# led_VDC.net
KiCad netlist of a schematic drawn in Altium Designer
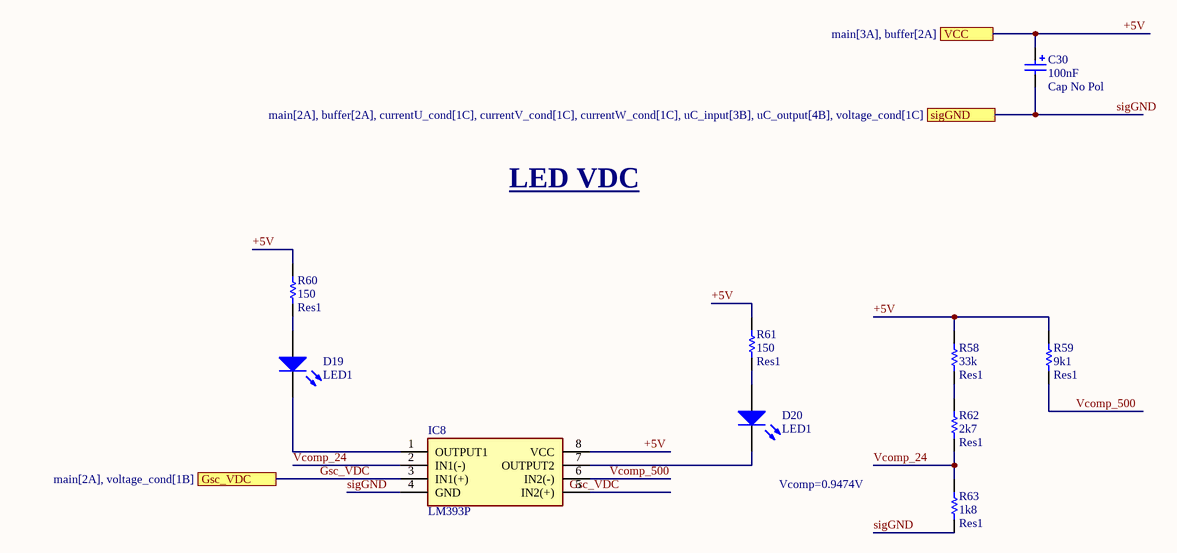
[diagram p0: led_VDC.SchDoc]

(export (version "E")
  (design (tool "Eeschema 10.0.6"))
  (components
    (comp (ref "C30")
      (value "Cap No Pol")
      (footprint "RAD-0.1_mod")
      (description "Polarized Capacitor (Radial)")
      (fields (field (name "ALTIUM_VALUE") "100nF") (field (name "PUBLISHER") "Altium Limited"))
      (libsource (lib "LABSTEPS_Project") (part "Cap No Pol"))
    )
    (comp (ref "D19")
      (value "LED1")
      (footprint "PIN2_mod")
      (description "Typical RED GaAs LED")
      (fields (field (name "PUBLISHER") "Altium Limited"))
      (libsource (lib "moded_symbol") (part "LED1"))
    )
    (comp (ref "D20")
      (value "LED1")
      (footprint "PIN2_mod")
      (description "Typical RED GaAs LED")
      (fields (field (name "PUBLISHER") "Altium Limited"))
      (libsource (lib "moded_symbol") (part "LED1"))
    )
    (comp (ref "IC8")
      (value "LM393P")
      (footprint "DIP-8_mod")
      (description "Integrated Circuit")
      (fields
        (field (name "MANUFACTURER_PART_NUMBER") "LM393N")
        (field (name "MOUSER PART NUMBER") "926-LM393N")
      )
      (libsource (lib "SamacSys") (part "LM393N"))
    )
    (comp (ref "R58")
      (value "Res1")
      (footprint "AXIAL-0.3_mod")
      (description "Resistor")
      (fields (field (name "ALTIUM_VALUE") "33k") (field (name "PUBLISHER") "Altium Limited"))
      (libsource (lib "LABSTEPS_Project") (part "Res1"))
    )
    (comp (ref "R59")
      (value "Res1")
      (footprint "AXIAL-0.3_mod")
      (description "Resistor")
      (fields (field (name "ALTIUM_VALUE") "9k1") (field (name "PUBLISHER") "Altium Limited"))
      (libsource (lib "LABSTEPS_Project") (part "Res1"))
    )
    (comp (ref "R60")
      (value "Res1")
      (footprint "AXIAL-0.3_mod")
      (description "Resistor")
      (fields (field (name "ALTIUM_VALUE") "150") (field (name "PUBLISHER") "Altium Limited"))
      (libsource (lib "LABSTEPS_Project") (part "Res1"))
    )
    (comp (ref "R61")
      (value "Res1")
      (footprint "AXIAL-0.3_mod")
      (description "Resistor")
      (fields (field (name "ALTIUM_VALUE") "150") (field (name "PUBLISHER") "Altium Limited"))
      (libsource (lib "LABSTEPS_Project") (part "Res1"))
    )
    (comp (ref "R62")
      (value "Res1")
      (footprint "AXIAL-0.3_mod")
      (description "Resistor")
      (fields (field (name "ALTIUM_VALUE") "2k7") (field (name "PUBLISHER") "Altium Limited"))
      (libsource (lib "LABSTEPS_Project") (part "Res1"))
    )
    (comp (ref "R63")
      (value "Res1")
      (footprint "AXIAL-0.3_mod")
      (description "Resistor")
      (fields (field (name "ALTIUM_VALUE") "1k8") (field (name "PUBLISHER") "Altium Limited"))
      (libsource (lib "LABSTEPS_Project") (part "Res1"))
    )
  )
  (nets
    (net (code "1") (name "/+5V") (class "Default")
      (node (ref "C30") (pin "1") (pinfunction "1_1") (pintype "passive"))
      (node (ref "IC8") (pin "8") (pinfunction "VCC_8") (pintype "passive"))
      (node (ref "R58") (pin "2") (pinfunction "2_2") (pintype "passive"))
      (node (ref "R59") (pin "2") (pinfunction "2_2") (pintype "passive"))
      (node (ref "R60") (pin "2") (pinfunction "2_2") (pintype "passive"))
      (node (ref "R61") (pin "2") (pinfunction "2_2") (pintype "passive"))
    )
    (net (code "2") (name "/Gsc_VDC") (class "Default")
      (node (ref "IC8") (pin "3") (pinfunction "IN1(+)_3") (pintype "passive"))
      (node (ref "IC8") (pin "5") (pinfunction "IN2(+)_5") (pintype "passive"))
    )
    (net (code "3") (name "/Vcomp_24") (class "Default")
      (node (ref "IC8") (pin "2") (pinfunction "IN1(-)_2") (pintype "passive"))
      (node (ref "R62") (pin "1") (pinfunction "1_1") (pintype "passive"))
      (node (ref "R63") (pin "2") (pinfunction "2_2") (pintype "passive"))
    )
    (net (code "4") (name "/Vcomp_500") (class "Default")
      (node (ref "IC8") (pin "6") (pinfunction "IN2(-)_6") (pintype "passive"))
      (node (ref "R59") (pin "1") (pinfunction "1_1") (pintype "passive"))
    )
    (net (code "5") (name "/sigGND") (class "Default")
      (node (ref "C30") (pin "2") (pinfunction "2_2") (pintype "passive"))
      (node (ref "IC8") (pin "4") (pinfunction "GND_4") (pintype "passive"))
      (node (ref "R63") (pin "1") (pinfunction "1_1") (pintype "passive"))
    )
    (net (code "6") (name "Net-(D19-A)") (class "Default")
      (node (ref "D19") (pin "1") (pinfunction "A_1") (pintype "passive"))
      (node (ref "R60") (pin "1") (pinfunction "1_1") (pintype "passive"))
    )
    (net (code "7") (name "Net-(D19-K)") (class "Default")
      (node (ref "D19") (pin "2") (pinfunction "K_2") (pintype "passive"))
      (node (ref "IC8") (pin "1") (pinfunction "OUTPUT1_1") (pintype "passive"))
    )
    (net (code "8") (name "Net-(D20-A)") (class "Default")
      (node (ref "D20") (pin "1") (pinfunction "A_1") (pintype "passive"))
      (node (ref "R61") (pin "1") (pinfunction "1_1") (pintype "passive"))
    )
    (net (code "9") (name "Net-(D20-K)") (class "Default")
      (node (ref "D20") (pin "2") (pinfunction "K_2") (pintype "passive"))
      (node (ref "IC8") (pin "7") (pinfunction "OUTPUT2_7") (pintype "passive"))
    )
    (net (code "10") (name "Net-(R58-Pad1)") (class "Default")
      (node (ref "R58") (pin "1") (pinfunction "1_1") (pintype "passive"))
      (node (ref "R62") (pin "2") (pinfunction "2_2") (pintype "passive"))
    )
  )
)
